# PowerSupply.net
KiCad netlist of a schematic drawn in EAGLE
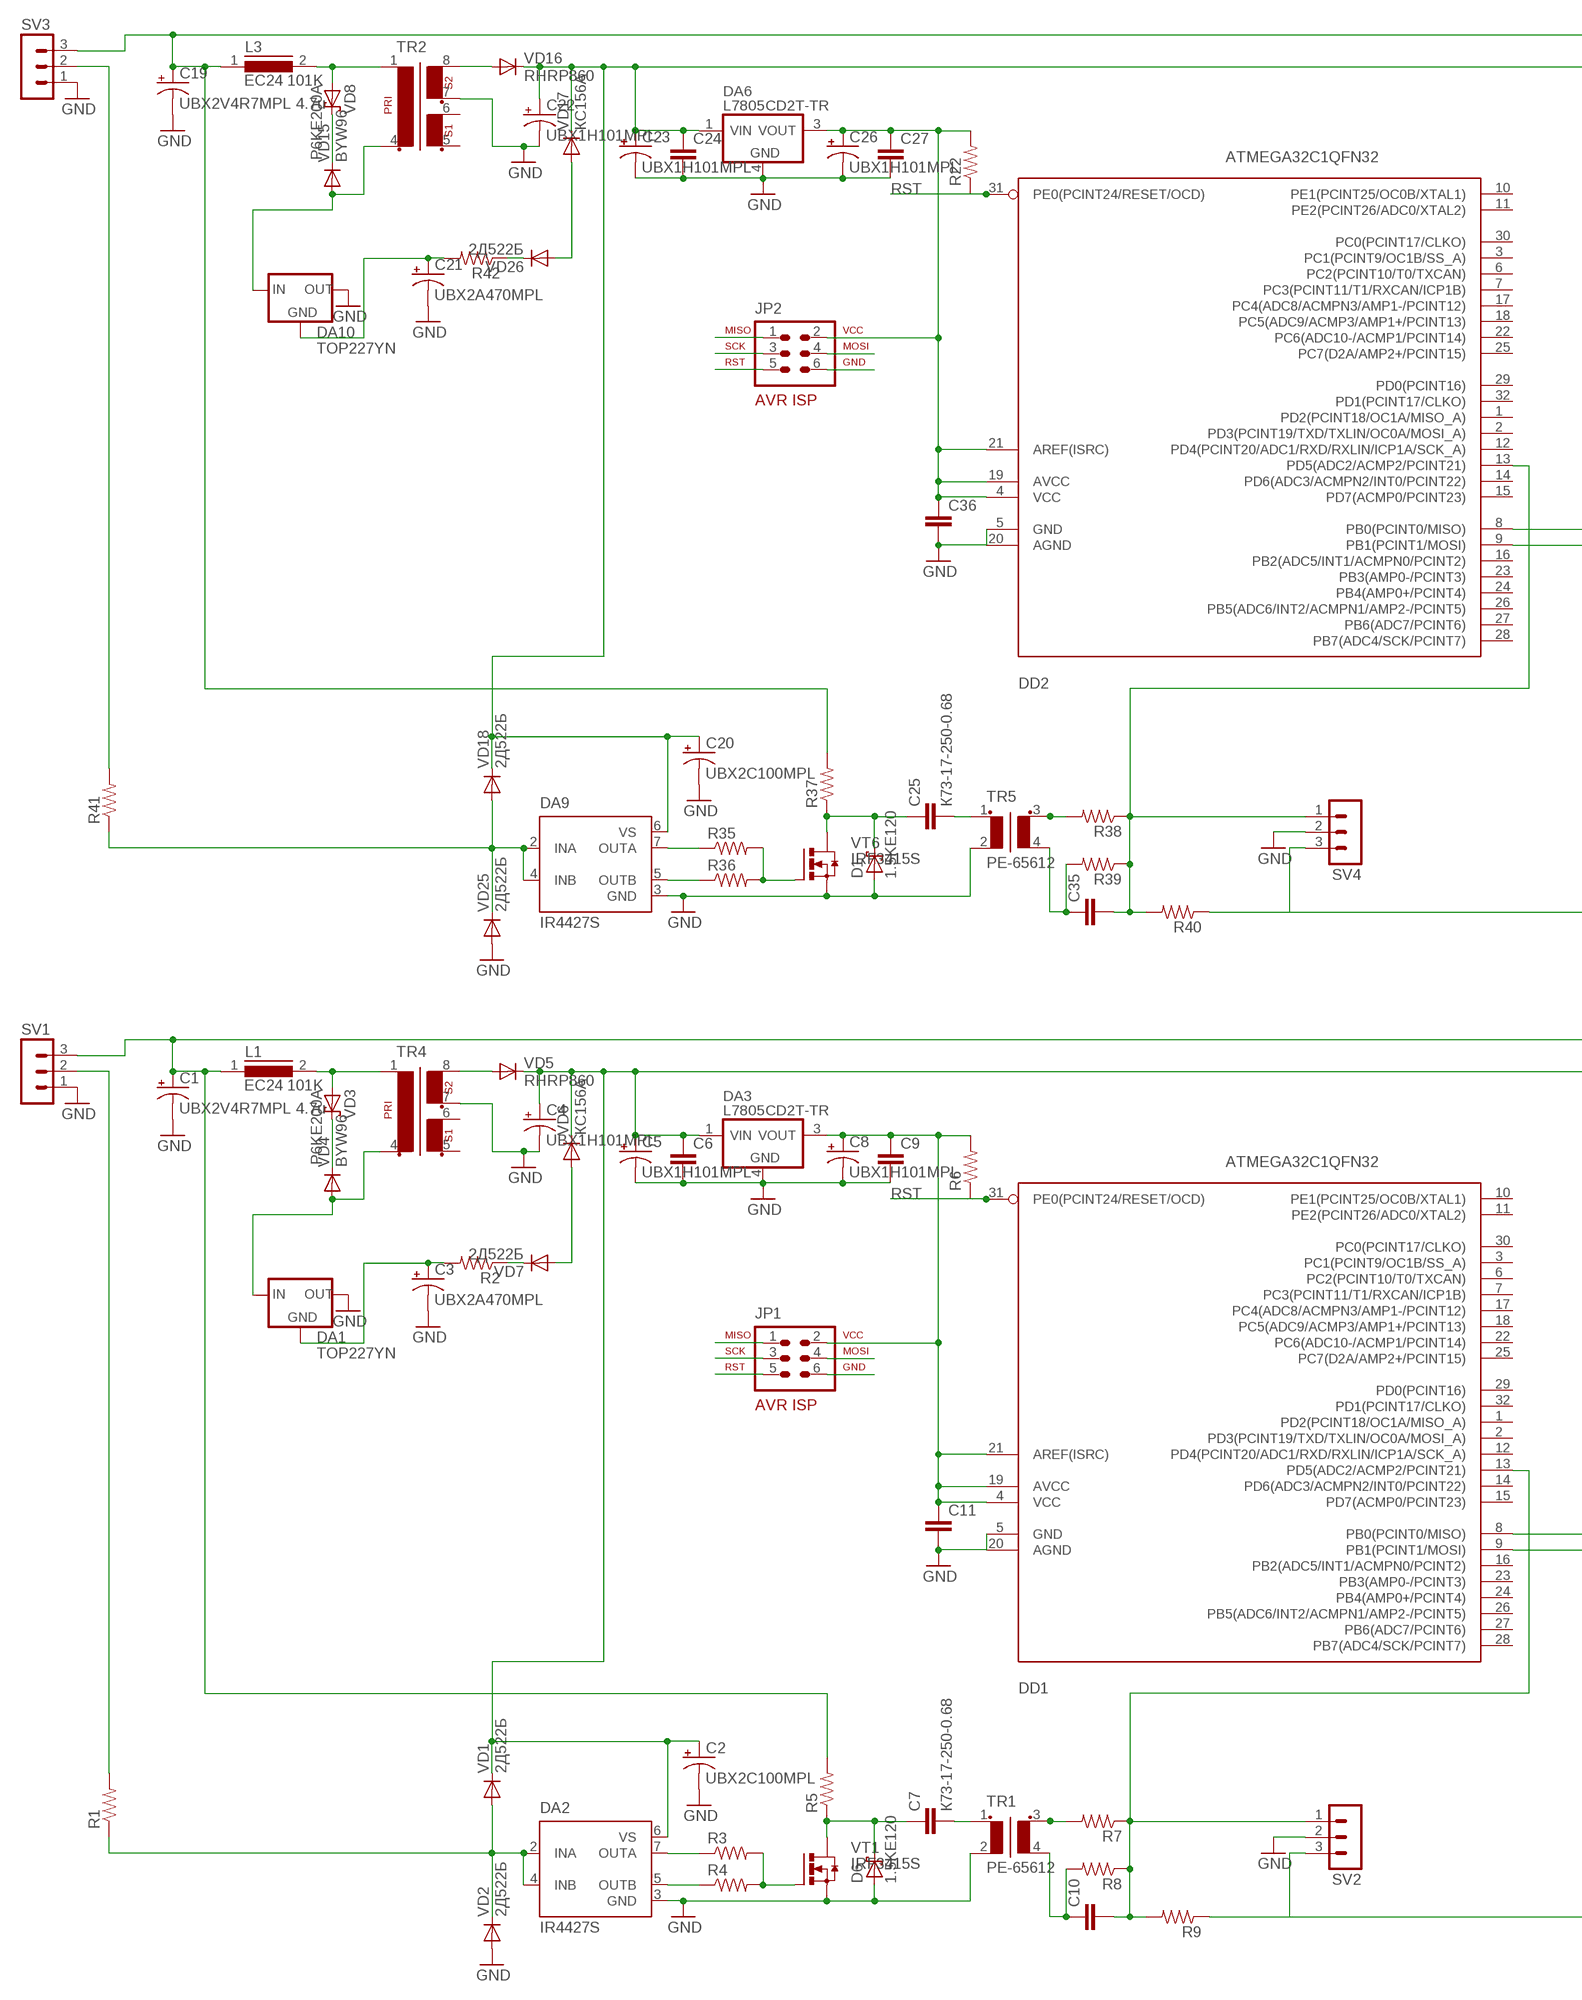
[diagram p0: schematic, sheet 1, part 1 of 2]
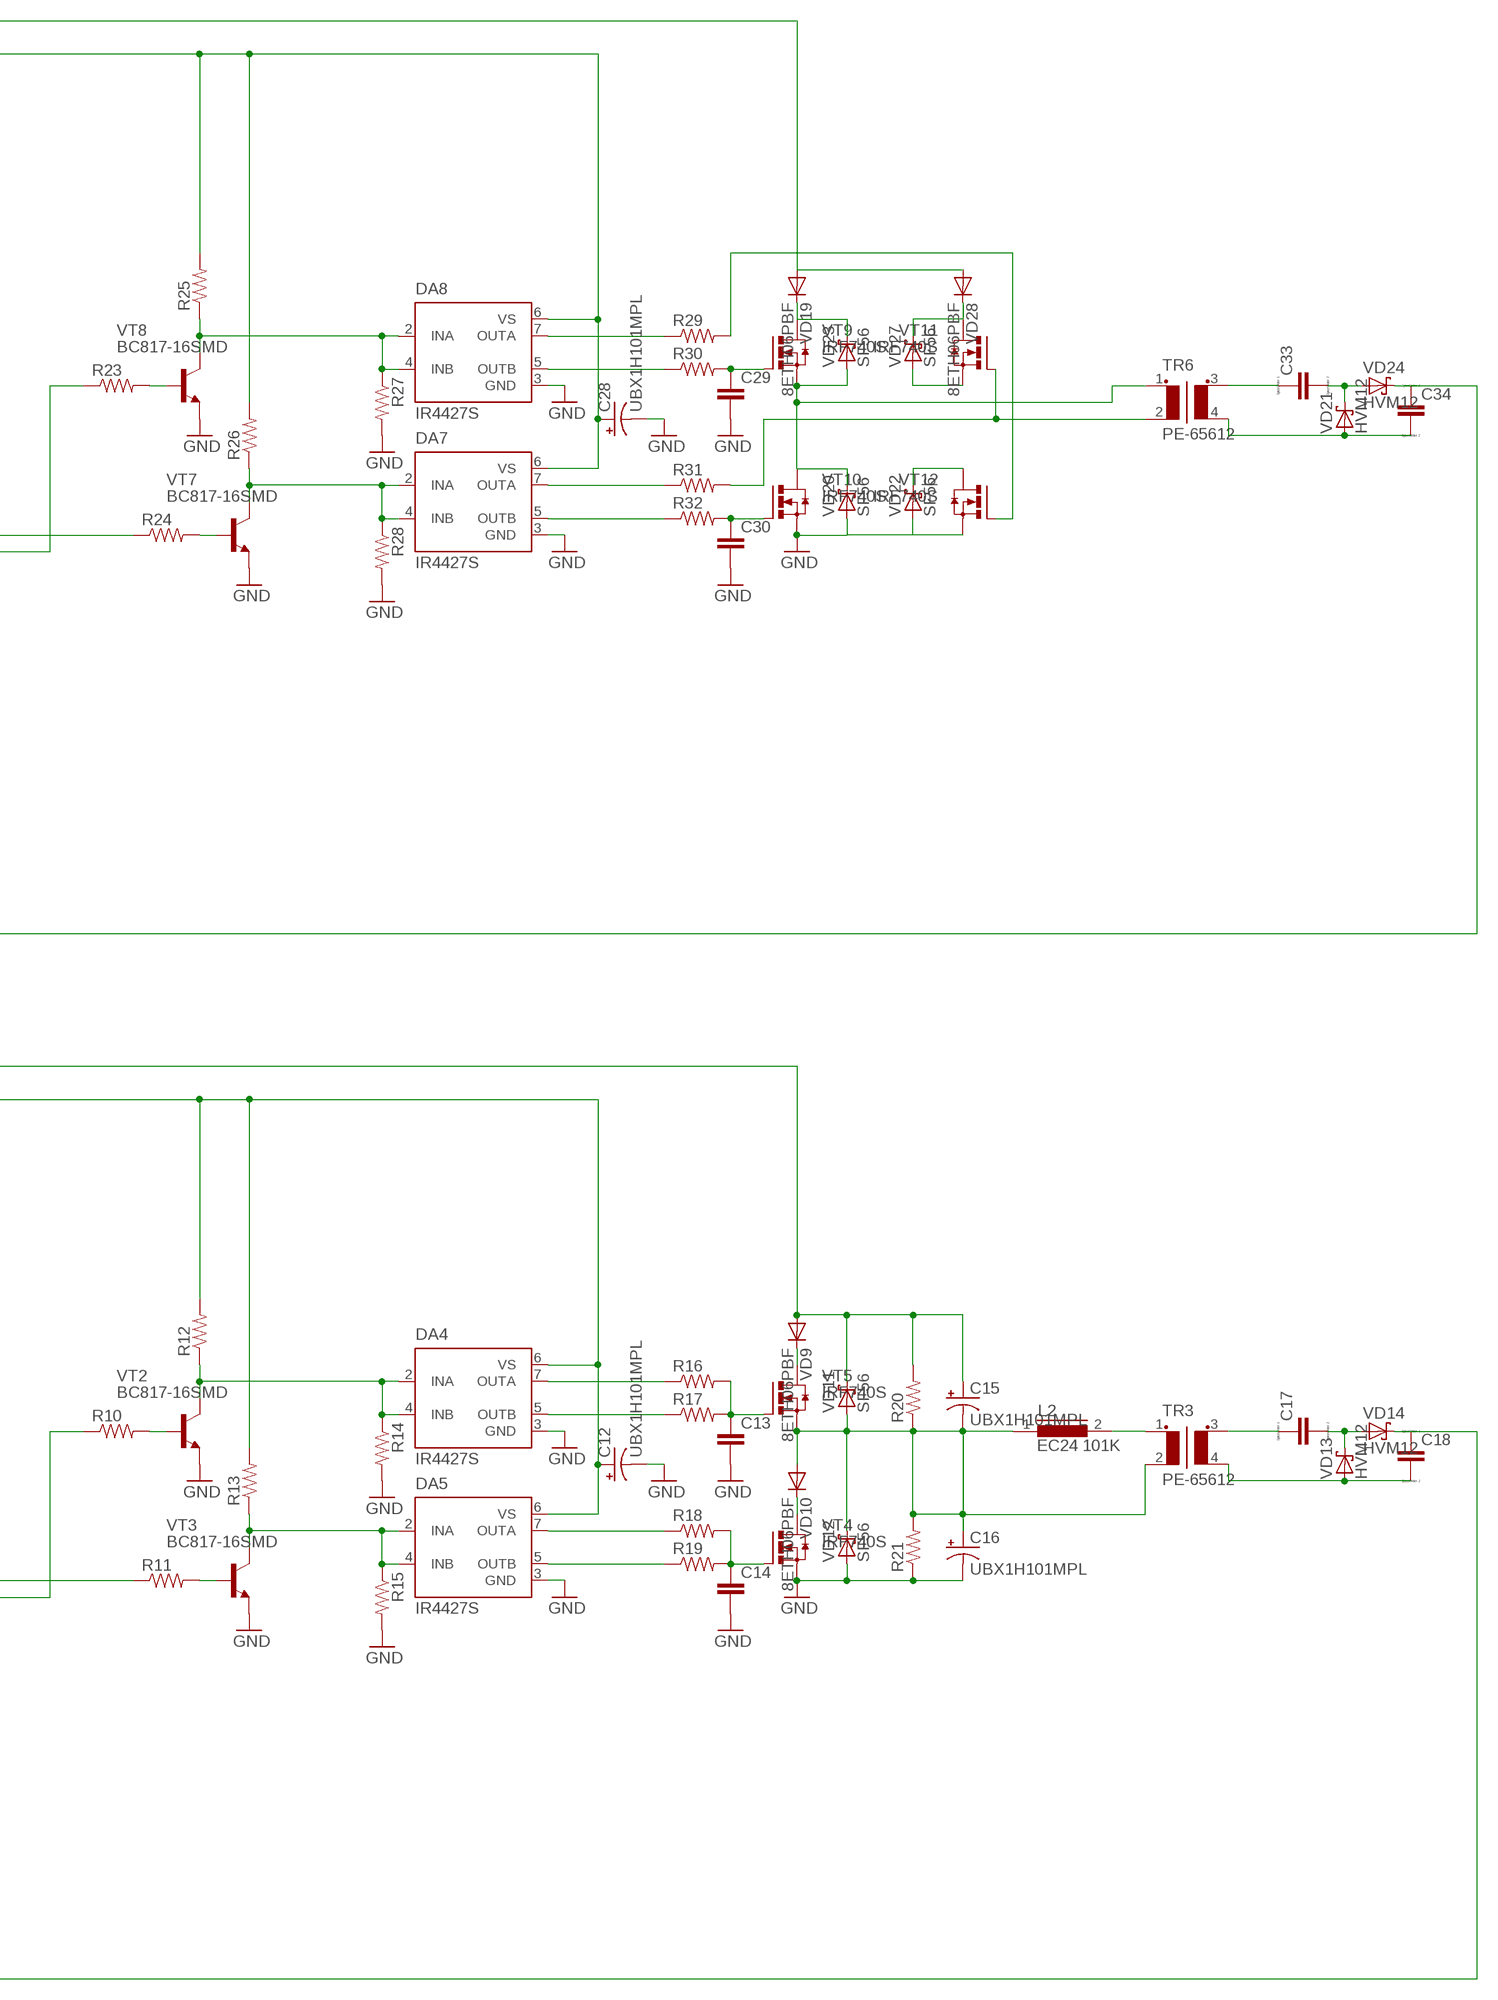
[diagram p1: schematic, sheet 1, part 2 of 2]

(export (version "E")
  (design (tool "Eeschema 10.0.6"))
  (components
    (comp (ref "C1")
      (value "UBX2V4R7MPL 4.7u")
      (footprint "eagle-import:CPOL-RADIAL-100UF-25V")
      (libsource (lib "eagle-import") (part "CAP_POLPTH1"))
    )
    (comp (ref "C2")
      (value "UBX2C100MPL")
      (footprint "eagle-import:CPOL-RADIAL-100UF-25V")
      (libsource (lib "eagle-import") (part "CAP_POLPTH1"))
    )
    (comp (ref "C3")
      (value "UBX2A470MPL")
      (footprint "eagle-import:CPOL-RADIAL-100UF-25V")
      (libsource (lib "eagle-import") (part "CAP_POLPTH1"))
    )
    (comp (ref "C4")
      (value "UBX1H101MPL")
      (footprint "eagle-import:CPOL-RADIAL-100UF-25V")
      (libsource (lib "eagle-import") (part "CAP_POLPTH1"))
    )
    (comp (ref "C5")
      (value "UBX1H101MPL")
      (footprint "eagle-import:CPOL-RADIAL-100UF-25V")
      (libsource (lib "eagle-import") (part "CAP_POLPTH1"))
    )
    (comp (ref "C6")
      (value "CAP1206")
      (footprint "eagle-import:1206")
      (libsource (lib "eagle-import") (part "CAP1206"))
    )
    (comp (ref "C7")
      (value "К73-17-250-0.68")
      (footprint "eagle-import:CAP-PTH-LARGE")
      (libsource (lib "eagle-import") (part "CAPPTH3"))
    )
    (comp (ref "C8")
      (value "UBX1H101MPL")
      (footprint "eagle-import:CPOL-RADIAL-100UF-25V")
      (libsource (lib "eagle-import") (part "CAP_POLPTH1"))
    )
    (comp (ref "C9")
      (value "CAP1206")
      (footprint "eagle-import:1206")
      (libsource (lib "eagle-import") (part "CAP1206"))
    )
    (comp (ref "C10")
      (value "CAP1206")
      (footprint "eagle-import:1206")
      (libsource (lib "eagle-import") (part "CAP1206"))
    )
    (comp (ref "C11")
      (value "CAP1206")
      (footprint "eagle-import:1206")
      (libsource (lib "eagle-import") (part "CAP1206"))
    )
    (comp (ref "C12")
      (value "UBX1H101MPL")
      (footprint "eagle-import:CPOL-RADIAL-100UF-25V")
      (libsource (lib "eagle-import") (part "CAP_POLPTH1"))
    )
    (comp (ref "C13")
      (value "CAP1206")
      (footprint "eagle-import:1206")
      (libsource (lib "eagle-import") (part "CAP1206"))
    )
    (comp (ref "C14")
      (value "CAP1206")
      (footprint "eagle-import:1206")
      (libsource (lib "eagle-import") (part "CAP1206"))
    )
    (comp (ref "C15")
      (value "UBX1H101MPL")
      (footprint "eagle-import:CPOL-RADIAL-100UF-25V")
      (libsource (lib "eagle-import") (part "CAP_POLPTH1"))
    )
    (comp (ref "C16")
      (value "UBX1H101MPL")
      (footprint "eagle-import:CPOL-RADIAL-100UF-25V")
      (libsource (lib "eagle-import") (part "CAP_POLPTH1"))
    )
    (comp (ref "C17")
      (value "CC1812")
      (footprint "eagle-import:C1812")
      (libsource (lib "eagle-import") (part "CC1812"))
    )
    (comp (ref "C18")
      (value "CC1812")
      (footprint "eagle-import:C1812")
      (libsource (lib "eagle-import") (part "CC1812"))
    )
    (comp (ref "C19")
      (value "UBX2V4R7MPL 4.7u")
      (footprint "eagle-import:CPOL-RADIAL-100UF-25V")
      (libsource (lib "eagle-import") (part "CAP_POLPTH1"))
    )
    (comp (ref "C20")
      (value "UBX2C100MPL")
      (footprint "eagle-import:CPOL-RADIAL-100UF-25V")
      (libsource (lib "eagle-import") (part "CAP_POLPTH1"))
    )
    (comp (ref "C21")
      (value "UBX2A470MPL")
      (footprint "eagle-import:CPOL-RADIAL-100UF-25V")
      (libsource (lib "eagle-import") (part "CAP_POLPTH1"))
    )
    (comp (ref "C22")
      (value "UBX1H101MPL")
      (footprint "eagle-import:CPOL-RADIAL-100UF-25V")
      (libsource (lib "eagle-import") (part "CAP_POLPTH1"))
    )
    (comp (ref "C23")
      (value "UBX1H101MPL")
      (footprint "eagle-import:CPOL-RADIAL-100UF-25V")
      (libsource (lib "eagle-import") (part "CAP_POLPTH1"))
    )
    (comp (ref "C24")
      (value "CAP1206")
      (footprint "eagle-import:1206")
      (libsource (lib "eagle-import") (part "CAP1206"))
    )
    (comp (ref "C25")
      (value "К73-17-250-0.68")
      (footprint "eagle-import:CAP-PTH-LARGE")
      (libsource (lib "eagle-import") (part "CAPPTH3"))
    )
    (comp (ref "C26")
      (value "UBX1H101MPL")
      (footprint "eagle-import:CPOL-RADIAL-100UF-25V")
      (libsource (lib "eagle-import") (part "CAP_POLPTH1"))
    )
    (comp (ref "C27")
      (value "CAP1206")
      (footprint "eagle-import:1206")
      (libsource (lib "eagle-import") (part "CAP1206"))
    )
    (comp (ref "C28")
      (value "UBX1H101MPL")
      (footprint "eagle-import:CPOL-RADIAL-100UF-25V")
      (libsource (lib "eagle-import") (part "CAP_POLPTH1"))
    )
    (comp (ref "C29")
      (value "CAP1206")
      (footprint "eagle-import:1206")
      (libsource (lib "eagle-import") (part "CAP1206"))
    )
    (comp (ref "C30")
      (value "CAP1206")
      (footprint "eagle-import:1206")
      (libsource (lib "eagle-import") (part "CAP1206"))
    )
    (comp (ref "C33")
      (value "CC1812")
      (footprint "eagle-import:C1812")
      (libsource (lib "eagle-import") (part "CC1812"))
    )
    (comp (ref "C34")
      (value "CC1812")
      (footprint "eagle-import:C1812")
      (libsource (lib "eagle-import") (part "CC1812"))
    )
    (comp (ref "C35")
      (value "CAP1206")
      (footprint "eagle-import:1206")
      (libsource (lib "eagle-import") (part "CAP1206"))
    )
    (comp (ref "C36")
      (value "CAP1206")
      (footprint "eagle-import:1206")
      (libsource (lib "eagle-import") (part "CAP1206"))
    )
    (comp (ref "D1")
      (value "1.5KE120")
      (footprint "eagle-import:CB417-15")
      (libsource (lib "eagle-import") (part "P6KEXX"))
    )
    (comp (ref "D6")
      (value "1.5KE120")
      (footprint "eagle-import:CB417-15")
      (libsource (lib "eagle-import") (part "P6KEXX"))
    )
    (comp (ref "DA1")
      (value "TOP227YN")
      (footprint "eagle-import:TO220S")
      (libsource (lib "eagle-import") (part "LM1086TO220V"))
    )
    (comp (ref "DA2")
      (value "IR4427S")
      (footprint "eagle-import:SO08")
      (fields (field (name "MF") "INTERNATIONAL RECTIFIER(IR)") (field (name "MPN") "IR4427STRPBF"))
      (libsource (lib "eagle-import") (part "IR4427S"))
    )
    (comp (ref "DA3")
      (value "L7805CD2T-TR")
      (footprint "eagle-import:D2PAK-3")
      (libsource (lib "eagle-import") (part "MC78D2T05"))
    )
    (comp (ref "DA4")
      (value "IR4427S")
      (footprint "eagle-import:SO08")
      (fields (field (name "MF") "INTERNATIONAL RECTIFIER(IR)") (field (name "MPN") "IR4427STRPBF"))
      (libsource (lib "eagle-import") (part "IR4427S"))
    )
    (comp (ref "DA5")
      (value "IR4427S")
      (footprint "eagle-import:SO08")
      (fields (field (name "MF") "INTERNATIONAL RECTIFIER(IR)") (field (name "MPN") "IR4427STRPBF"))
      (libsource (lib "eagle-import") (part "IR4427S"))
    )
    (comp (ref "DA6")
      (value "L7805CD2T-TR")
      (footprint "eagle-import:D2PAK-3")
      (libsource (lib "eagle-import") (part "MC78D2T05"))
    )
    (comp (ref "DA7")
      (value "IR4427S")
      (footprint "eagle-import:SO08")
      (fields (field (name "MF") "INTERNATIONAL RECTIFIER(IR)") (field (name "MPN") "IR4427STRPBF"))
      (libsource (lib "eagle-import") (part "IR4427S"))
    )
    (comp (ref "DA8")
      (value "IR4427S")
      (footprint "eagle-import:SO08")
      (fields (field (name "MF") "INTERNATIONAL RECTIFIER(IR)") (field (name "MPN") "IR4427STRPBF"))
      (libsource (lib "eagle-import") (part "IR4427S"))
    )
    (comp (ref "DA9")
      (value "IR4427S")
      (footprint "eagle-import:SO08")
      (fields (field (name "MF") "INTERNATIONAL RECTIFIER(IR)") (field (name "MPN") "IR4427STRPBF"))
      (libsource (lib "eagle-import") (part "IR4427S"))
    )
    (comp (ref "DA10")
      (value "TOP227YN")
      (footprint "eagle-import:TO220S")
      (libsource (lib "eagle-import") (part "LM1086TO220V"))
    )
    (comp (ref "DD1")
      (value "ATMEGA32C1QFN32")
      (footprint "eagle-import:QFN32")
      (libsource (lib "eagle-import") (part "ATMEGA32C1QFN32"))
    )
    (comp (ref "DD2")
      (value "ATMEGA32C1QFN32")
      (footprint "eagle-import:QFN32")
      (libsource (lib "eagle-import") (part "ATMEGA32C1QFN32"))
    )
    (comp (ref "JP1")
      (value "AVR-ISP-6VERT")
      (footprint "eagle-import:AVR-ISP-6")
      (libsource (lib "eagle-import") (part "AVR-ISP-6VERT"))
    )
    (comp (ref "JP2")
      (value "AVR-ISP-6VERT")
      (footprint "eagle-import:AVR-ISP-6")
      (libsource (lib "eagle-import") (part "AVR-ISP-6VERT"))
    )
    (comp (ref "L1")
      (value "EC24 101K")
      (footprint "eagle-import:MMICC7")
      (libsource (lib "eagle-import") (part "MMICC7"))
    )
    (comp (ref "L2")
      (value "EC24 101K")
      (footprint "eagle-import:MMICC7")
      (libsource (lib "eagle-import") (part "MMICC7"))
    )
    (comp (ref "L3")
      (value "EC24 101K")
      (footprint "eagle-import:MMICC7")
      (libsource (lib "eagle-import") (part "MMICC7"))
    )
    (comp (ref "R1")
      (value "RESISTOR1206")
      (footprint "eagle-import:1206")
      (libsource (lib "eagle-import") (part "RESISTOR1206"))
    )
    (comp (ref "R2")
      (value "RESISTOR1206")
      (footprint "eagle-import:1206")
      (libsource (lib "eagle-import") (part "RESISTOR1206"))
    )
    (comp (ref "R3")
      (value "RESISTOR1206")
      (footprint "eagle-import:1206")
      (libsource (lib "eagle-import") (part "RESISTOR1206"))
    )
    (comp (ref "R4")
      (value "RESISTOR1206")
      (footprint "eagle-import:1206")
      (libsource (lib "eagle-import") (part "RESISTOR1206"))
    )
    (comp (ref "R5")
      (value "RESISTOR1206")
      (footprint "eagle-import:1206")
      (libsource (lib "eagle-import") (part "RESISTOR1206"))
    )
    (comp (ref "R6")
      (value "RESISTOR1206")
      (footprint "eagle-import:1206")
      (libsource (lib "eagle-import") (part "RESISTOR1206"))
    )
    (comp (ref "R7")
      (value "RESISTOR1206")
      (footprint "eagle-import:1206")
      (libsource (lib "eagle-import") (part "RESISTOR1206"))
    )
    (comp (ref "R8")
      (value "RESISTOR1206")
      (footprint "eagle-import:1206")
      (libsource (lib "eagle-import") (part "RESISTOR1206"))
    )
    (comp (ref "R9")
      (value "RESISTOR1206")
      (footprint "eagle-import:1206")
      (libsource (lib "eagle-import") (part "RESISTOR1206"))
    )
    (comp (ref "R10")
      (value "RESISTOR1206")
      (footprint "eagle-import:1206")
      (libsource (lib "eagle-import") (part "RESISTOR1206"))
    )
    (comp (ref "R11")
      (value "RESISTOR1206")
      (footprint "eagle-import:1206")
      (libsource (lib "eagle-import") (part "RESISTOR1206"))
    )
    (comp (ref "R12")
      (value "RESISTOR1206")
      (footprint "eagle-import:1206")
      (libsource (lib "eagle-import") (part "RESISTOR1206"))
    )
    (comp (ref "R13")
      (value "RESISTOR1206")
      (footprint "eagle-import:1206")
      (libsource (lib "eagle-import") (part "RESISTOR1206"))
    )
    (comp (ref "R14")
      (value "RESISTOR1206")
      (footprint "eagle-import:1206")
      (libsource (lib "eagle-import") (part "RESISTOR1206"))
    )
    (comp (ref "R15")
      (value "RESISTOR1206")
      (footprint "eagle-import:1206")
      (libsource (lib "eagle-import") (part "RESISTOR1206"))
    )
    (comp (ref "R16")
      (value "RESISTOR1206")
      (footprint "eagle-import:1206")
      (libsource (lib "eagle-import") (part "RESISTOR1206"))
    )
    (comp (ref "R17")
      (value "RESISTOR1206")
      (footprint "eagle-import:1206")
      (libsource (lib "eagle-import") (part "RESISTOR1206"))
    )
    (comp (ref "R18")
      (value "RESISTOR1206")
      (footprint "eagle-import:1206")
      (libsource (lib "eagle-import") (part "RESISTOR1206"))
    )
    (comp (ref "R19")
      (value "RESISTOR1206")
      (footprint "eagle-import:1206")
      (libsource (lib "eagle-import") (part "RESISTOR1206"))
    )
    (comp (ref "R20")
      (value "RESISTOR1206")
      (footprint "eagle-import:1206")
      (libsource (lib "eagle-import") (part "RESISTOR1206"))
    )
    (comp (ref "R21")
      (value "RESISTOR1206")
      (footprint "eagle-import:1206")
      (libsource (lib "eagle-import") (part "RESISTOR1206"))
    )
    (comp (ref "R22")
      (value "RESISTOR1206")
      (footprint "eagle-import:1206")
      (libsource (lib "eagle-import") (part "RESISTOR1206"))
    )
    (comp (ref "R23")
      (value "RESISTOR1206")
      (footprint "eagle-import:1206")
      (libsource (lib "eagle-import") (part "RESISTOR1206"))
    )
    (comp (ref "R24")
      (value "RESISTOR1206")
      (footprint "eagle-import:1206")
      (libsource (lib "eagle-import") (part "RESISTOR1206"))
    )
    (comp (ref "R25")
      (value "RESISTOR1206")
      (footprint "eagle-import:1206")
      (libsource (lib "eagle-import") (part "RESISTOR1206"))
    )
    (comp (ref "R26")
      (value "RESISTOR1206")
      (footprint "eagle-import:1206")
      (libsource (lib "eagle-import") (part "RESISTOR1206"))
    )
    (comp (ref "R27")
      (value "RESISTOR1206")
      (footprint "eagle-import:1206")
      (libsource (lib "eagle-import") (part "RESISTOR1206"))
    )
    (comp (ref "R28")
      (value "RESISTOR1206")
      (footprint "eagle-import:1206")
      (libsource (lib "eagle-import") (part "RESISTOR1206"))
    )
    (comp (ref "R29")
      (value "RESISTOR1206")
      (footprint "eagle-import:1206")
      (libsource (lib "eagle-import") (part "RESISTOR1206"))
    )
    (comp (ref "R30")
      (value "RESISTOR1206")
      (footprint "eagle-import:1206")
      (libsource (lib "eagle-import") (part "RESISTOR1206"))
    )
    (comp (ref "R31")
      (value "RESISTOR1206")
      (footprint "eagle-import:1206")
      (libsource (lib "eagle-import") (part "RESISTOR1206"))
    )
    (comp (ref "R32")
      (value "RESISTOR1206")
      (footprint "eagle-import:1206")
      (libsource (lib "eagle-import") (part "RESISTOR1206"))
    )
    (comp (ref "R35")
      (value "RESISTOR1206")
      (footprint "eagle-import:1206")
      (libsource (lib "eagle-import") (part "RESISTOR1206"))
    )
    (comp (ref "R36")
      (value "RESISTOR1206")
      (footprint "eagle-import:1206")
      (libsource (lib "eagle-import") (part "RESISTOR1206"))
    )
    (comp (ref "R37")
      (value "RESISTOR1206")
      (footprint "eagle-import:1206")
      (libsource (lib "eagle-import") (part "RESISTOR1206"))
    )
    (comp (ref "R38")
      (value "RESISTOR1206")
      (footprint "eagle-import:1206")
      (libsource (lib "eagle-import") (part "RESISTOR1206"))
    )
    (comp (ref "R39")
      (value "RESISTOR1206")
      (footprint "eagle-import:1206")
      (libsource (lib "eagle-import") (part "RESISTOR1206"))
    )
    (comp (ref "R40")
      (value "RESISTOR1206")
      (footprint "eagle-import:1206")
      (libsource (lib "eagle-import") (part "RESISTOR1206"))
    )
    (comp (ref "R41")
      (value "RESISTOR1206")
      (footprint "eagle-import:1206")
      (libsource (lib "eagle-import") (part "RESISTOR1206"))
    )
    (comp (ref "R42")
      (value "RESISTOR1206")
      (footprint "eagle-import:1206")
      (libsource (lib "eagle-import") (part "RESISTOR1206"))
    )
    (comp (ref "SV1")
      (value "MA03-1")
      (footprint "eagle-import:MA03-1")
      (libsource (lib "eagle-import") (part "MA03-1"))
    )
    (comp (ref "SV2")
      (value "MA03-1")
      (footprint "eagle-import:MA03-1")
      (libsource (lib "eagle-import") (part "MA03-1"))
    )
    (comp (ref "SV3")
      (value "MA03-1")
      (footprint "eagle-import:MA03-1")
      (libsource (lib "eagle-import") (part "MA03-1"))
    )
    (comp (ref "SV4")
      (value "MA03-1")
      (footprint "eagle-import:MA03-1")
      (libsource (lib "eagle-import") (part "MA03-1"))
    )
    (comp (ref "TR1")
      (value "PE-65612")
      (footprint "eagle-import:PE-65612")
      (libsource (lib "eagle-import") (part "PE-65612"))
    )
    (comp (ref "TR2")
      (value "EE20-2")
      (footprint "eagle-import:EE20-2")
      (libsource (lib "eagle-import") (part "EE20-2"))
    )
    (comp (ref "TR3")
      (value "PE-65612")
      (footprint "eagle-import:PE-65612")
      (libsource (lib "eagle-import") (part "PE-65612"))
    )
    (comp (ref "TR4")
      (value "EE20-2")
      (footprint "eagle-import:EE20-2")
      (libsource (lib "eagle-import") (part "EE20-2"))
    )
    (comp (ref "TR5")
      (value "PE-65612")
      (footprint "eagle-import:PE-65612")
      (libsource (lib "eagle-import") (part "PE-65612"))
    )
    (comp (ref "TR6")
      (value "PE-65612")
      (footprint "eagle-import:PE-65612")
      (libsource (lib "eagle-import") (part "PE-65612"))
    )
    (comp (ref "VD1")
      (value "2Д522Б")
      (footprint "eagle-import:DO35-10")
      (libsource (lib "eagle-import") (part "1N4446"))
    )
    (comp (ref "VD2")
      (value "2Д522Б")
      (footprint "eagle-import:DO35-10")
      (libsource (lib "eagle-import") (part "1N4446"))
    )
    (comp (ref "VD3")
      (value "P6KE200A")
      (footprint "eagle-import:CB417-15")
      (libsource (lib "eagle-import") (part "P6KEXX"))
    )
    (comp (ref "VD4")
      (value "BYW96")
      (footprint "eagle-import:SOD64-10")
      (libsource (lib "eagle-import") (part "BYW96"))
    )
    (comp (ref "VD5")
      (value "RHRP860")
      (footprint "eagle-import:TO220ACS")
      (libsource (lib "eagle-import") (part "DIODE-TO220V"))
    )
    (comp (ref "VD6")
      (value "КС156А")
      (footprint "eagle-import:DO35-10")
      (libsource (lib "eagle-import") (part "1N4446"))
    )
    (comp (ref "VD7")
      (value "2Д522Б")
      (footprint "eagle-import:DO35-10")
      (libsource (lib "eagle-import") (part "1N4446"))
    )
    (comp (ref "VD8")
      (value "P6KE200A")
      (footprint "eagle-import:CB417-15")
      (libsource (lib "eagle-import") (part "P6KEXX"))
    )
    (comp (ref "VD9")
      (value "8ETH06PBF")
      (footprint "eagle-import:TO220ACS")
      (libsource (lib "eagle-import") (part "DIODE-TO220V"))
    )
    (comp (ref "VD10")
      (value "8ETH06PBF")
      (footprint "eagle-import:TO220ACS")
      (libsource (lib "eagle-import") (part "DIODE-TO220V"))
    )
    (comp (ref "VD11")
      (value "SF56")
      (footprint "eagle-import:CB417-15")
      (libsource (lib "eagle-import") (part "P6KEXX"))
    )
    (comp (ref "VD12")
      (value "SF56")
      (footprint "eagle-import:CB417-15")
      (libsource (lib "eagle-import") (part "P6KEXX"))
    )
    (comp (ref "VD13")
      (value "HVM12")
      (footprint "eagle-import:CB417-15")
      (libsource (lib "eagle-import") (part "P6KEXX"))
    )
    (comp (ref "VD14")
      (value "HVM12")
      (footprint "eagle-import:CB417-15")
      (libsource (lib "eagle-import") (part "P6KEXX"))
    )
    (comp (ref "VD15")
      (value "BYW96")
      (footprint "eagle-import:SOD64-10")
      (libsource (lib "eagle-import") (part "BYW96"))
    )
    (comp (ref "VD16")
      (value "RHRP860")
      (footprint "eagle-import:TO220ACS")
      (libsource (lib "eagle-import") (part "DIODE-TO220V"))
    )
    (comp (ref "VD17")
      (value "КС156А")
      (footprint "eagle-import:DO35-10")
      (libsource (lib "eagle-import") (part "1N4446"))
    )
    (comp (ref "VD18")
      (value "2Д522Б")
      (footprint "eagle-import:DO35-10")
      (libsource (lib "eagle-import") (part "1N4446"))
    )
    (comp (ref "VD19")
      (value "8ETH06PBF")
      (footprint "eagle-import:TO220ACS")
      (libsource (lib "eagle-import") (part "DIODE-TO220V"))
    )
    (comp (ref "VD20")
      (value "SF56")
      (footprint "eagle-import:CB417-15")
      (libsource (lib "eagle-import") (part "P6KEXX"))
    )
    (comp (ref "VD21")
      (value "HVM12")
      (footprint "eagle-import:CB417-15")
      (libsource (lib "eagle-import") (part "P6KEXX"))
    )
    (comp (ref "VD22")
      (value "SF56")
      (footprint "eagle-import:CB417-15")
      (libsource (lib "eagle-import") (part "P6KEXX"))
    )
    (comp (ref "VD23")
      (value "SF56")
      (footprint "eagle-import:CB417-15")
      (libsource (lib "eagle-import") (part "P6KEXX"))
    )
    (comp (ref "VD24")
      (value "HVM12")
      (footprint "eagle-import:CB417-15")
      (libsource (lib "eagle-import") (part "P6KEXX"))
    )
    (comp (ref "VD25")
      (value "2Д522Б")
      (footprint "eagle-import:DO35-10")
      (libsource (lib "eagle-import") (part "1N4446"))
    )
    (comp (ref "VD26")
      (value "2Д522Б")
      (footprint "eagle-import:DO35-10")
      (libsource (lib "eagle-import") (part "1N4446"))
    )
    (comp (ref "VD27")
      (value "SF56")
      (footprint "eagle-import:CB417-15")
      (libsource (lib "eagle-import") (part "P6KEXX"))
    )
    (comp (ref "VD28")
      (value "8ETH06PBF")
      (footprint "eagle-import:TO220ACS")
      (libsource (lib "eagle-import") (part "DIODE-TO220V"))
    )
    (comp (ref "VT1")
      (value "IRF3415S")
      (footprint "eagle-import:D2PACK")
      (libsource (lib "eagle-import") (part "IRF3704S"))
    )
    (comp (ref "VT2")
      (value "BC817-16SMD")
      (footprint "eagle-import:SOT23-BEC")
      (libsource (lib "eagle-import") (part "BC817SMD-16"))
    )
    (comp (ref "VT3")
      (value "BC817-16SMD")
      (footprint "eagle-import:SOT23-BEC")
      (libsource (lib "eagle-import") (part "BC817SMD-16"))
    )
    (comp (ref "VT4")
      (value "IRF740S")
      (footprint "eagle-import:D2PACK")
      (libsource (lib "eagle-import") (part "IRF3704S"))
    )
    (comp (ref "VT5")
      (value "IRF740S")
      (footprint "eagle-import:D2PACK")
      (libsource (lib "eagle-import") (part "IRF3704S"))
    )
    (comp (ref "VT6")
      (value "IRF3415S")
      (footprint "eagle-import:D2PACK")
      (libsource (lib "eagle-import") (part "IRF3704S"))
    )
    (comp (ref "VT7")
      (value "BC817-16SMD")
      (footprint "eagle-import:SOT23-BEC")
      (libsource (lib "eagle-import") (part "BC817SMD-16"))
    )
    (comp (ref "VT8")
      (value "BC817-16SMD")
      (footprint "eagle-import:SOT23-BEC")
      (libsource (lib "eagle-import") (part "BC817SMD-16"))
    )
    (comp (ref "VT9")
      (value "IRF740S")
      (footprint "eagle-import:D2PACK")
      (libsource (lib "eagle-import") (part "IRF3704S"))
    )
    (comp (ref "VT10")
      (value "IRF740S")
      (footprint "eagle-import:D2PACK")
      (libsource (lib "eagle-import") (part "IRF3704S"))
    )
    (comp (ref "VT11")
      (value "IRF740S")
      (footprint "eagle-import:D2PACK")
      (libsource (lib "eagle-import") (part "IRF3704S"))
    )
    (comp (ref "VT12")
      (value "IRF740S")
      (footprint "eagle-import:D2PACK")
      (libsource (lib "eagle-import") (part "IRF3704S"))
    )
  )
  (nets
    (net (code "1") (name "/MISO") (class "Default")
      (node (ref "DD1") (pin "8") (pinfunction "PB0(PCINT0/MISO)_8") (pintype "bidirectional"))
      (node (ref "JP1") (pin "1") (pinfunction "1_1") (pintype "passive"))
      (node (ref "R11") (pin "1") (pinfunction "1_1") (pintype "passive"))
    )
    (net (code "2") (name "/MISO1") (class "Default")
      (node (ref "DD2") (pin "8") (pinfunction "PB0(PCINT0/MISO)_8") (pintype "bidirectional"))
      (node (ref "JP2") (pin "1") (pinfunction "1_1") (pintype "passive"))
      (node (ref "R24") (pin "1") (pinfunction "1_1") (pintype "passive"))
    )
    (net (code "3") (name "/MOSI") (class "Default")
      (node (ref "DD1") (pin "9") (pinfunction "PB1(PCINT1/MOSI)_9") (pintype "bidirectional"))
      (node (ref "JP1") (pin "4") (pinfunction "4_4") (pintype "passive"))
      (node (ref "R10") (pin "1") (pinfunction "1_1") (pintype "passive"))
    )
    (net (code "4") (name "/MOSI1") (class "Default")
      (node (ref "DD2") (pin "9") (pinfunction "PB1(PCINT1/MOSI)_9") (pintype "bidirectional"))
      (node (ref "JP2") (pin "4") (pinfunction "4_4") (pintype "passive"))
      (node (ref "R23") (pin "1") (pinfunction "1_1") (pintype "passive"))
    )
    (net (code "5") (name "/RST") (class "Default")
      (node (ref "DD1") (pin "31") (pinfunction "PE0(PCINT24/RESET/OCD)_31") (pintype "bidirectional"))
      (node (ref "DD2") (pin "31") (pinfunction "PE0(PCINT24/RESET/OCD)_31") (pintype "bidirectional"))
      (node (ref "JP1") (pin "5") (pinfunction "5_5") (pintype "passive"))
      (node (ref "JP2") (pin "5") (pinfunction "5_5") (pintype "passive"))
      (node (ref "R22") (pin "1") (pinfunction "1_1") (pintype "passive"))
      (node (ref "R6") (pin "1") (pinfunction "1_1") (pintype "passive"))
    )
    (net (code "6") (name "/VOUT") (class "Default")
      (node (ref "C11") (pin "1") (pinfunction "1_1") (pintype "passive"))
      (node (ref "C26") (pin "1") (pinfunction "+_1") (pintype "passive"))
      (node (ref "C27") (pin "1") (pinfunction "1_1") (pintype "passive"))
      (node (ref "C36") (pin "1") (pinfunction "1_1") (pintype "passive"))
      (node (ref "C8") (pin "1") (pinfunction "+_1") (pintype "passive"))
      (node (ref "C9") (pin "1") (pinfunction "1_1") (pintype "passive"))
      (node (ref "DA3") (pin "3") (pinfunction "VOUT_3") (pintype "power_in"))
      (node (ref "DA6") (pin "3") (pinfunction "VOUT_3") (pintype "power_in"))
      (node (ref "DD1") (pin "19") (pinfunction "AVCC_19") (pintype "bidirectional"))
      (node (ref "DD1") (pin "21") (pinfunction "AREF(ISRC)_21") (pintype "bidirectional"))
      (node (ref "DD1") (pin "4") (pinfunction "VCC_4") (pintype "bidirectional"))
      (node (ref "DD2") (pin "19") (pinfunction "AVCC_19") (pintype "bidirectional"))
      (node (ref "DD2") (pin "21") (pinfunction "AREF(ISRC)_21") (pintype "bidirectional"))
      (node (ref "DD2") (pin "4") (pinfunction "VCC_4") (pintype "bidirectional"))
      (node (ref "JP1") (pin "2") (pinfunction "2_2") (pintype "passive"))
      (node (ref "JP2") (pin "2") (pinfunction "2_2") (pintype "passive"))
      (node (ref "R22") (pin "2") (pinfunction "2_2") (pintype "passive"))
      (node (ref "R6") (pin "2") (pinfunction "2_2") (pintype "passive"))
    )
    (net (code "7") (name "GND") (class "Default")
      (node (ref "C1") (pin "2") (pinfunction "-_2") (pintype "passive"))
      (node (ref "C11") (pin "2") (pinfunction "2_2") (pintype "passive"))
      (node (ref "C12") (pin "2") (pinfunction "-_2") (pintype "passive"))
      (node (ref "C13") (pin "2") (pinfunction "2_2") (pintype "passive"))
      (node (ref "C14") (pin "2") (pinfunction "2_2") (pintype "passive"))
      (node (ref "C16") (pin "2") (pinfunction "-_2") (pintype "passive"))
      (node (ref "C19") (pin "2") (pinfunction "-_2") (pintype "passive"))
      (node (ref "C2") (pin "2") (pinfunction "-_2") (pintype "passive"))
      (node (ref "C20") (pin "2") (pinfunction "-_2") (pintype "passive"))
      (node (ref "C21") (pin "2") (pinfunction "-_2") (pintype "passive"))
      (node (ref "C22") (pin "2") (pinfunction "-_2") (pintype "passive"))
      (node (ref "C23") (pin "2") (pinfunction "-_2") (pintype "passive"))
      (node (ref "C24") (pin "2") (pinfunction "2_2") (pintype "passive"))
      (node (ref "C26") (pin "2") (pinfunction "-_2") (pintype "passive"))
      (node (ref "C27") (pin "2") (pinfunction "2_2") (pintype "passive"))
      (node (ref "C28") (pin "2") (pinfunction "-_2") (pintype "passive"))
      (node (ref "C29") (pin "2") (pinfunction "2_2") (pintype "passive"))
      (node (ref "C3") (pin "2") (pinfunction "-_2") (pintype "passive"))
      (node (ref "C30") (pin "2") (pinfunction "2_2") (pintype "passive"))
      (node (ref "C36") (pin "2") (pinfunction "2_2") (pintype "passive"))
      (node (ref "C4") (pin "2") (pinfunction "-_2") (pintype "passive"))
      (node (ref "C5") (pin "2") (pinfunction "-_2") (pintype "passive"))
      (node (ref "C6") (pin "2") (pinfunction "2_2") (pintype "passive"))
      (node (ref "C8") (pin "2") (pinfunction "-_2") (pintype "passive"))
      (node (ref "C9") (pin "2") (pinfunction "2_2") (pintype "passive"))
      (node (ref "D1") (pin "A") (pinfunction "A_A") (pintype "passive"))
      (node (ref "D6") (pin "A") (pinfunction "A_A") (pintype "passive"))
      (node (ref "DA1") (pin "2") (pinfunction "OUT_2") (pintype "passive"))
      (node (ref "DA10") (pin "2") (pinfunction "OUT_2") (pintype "passive"))
      (node (ref "DA2") (pin "3") (pinfunction "GND_3") (pintype "power_in"))
      (node (ref "DA3") (pin "4") (pinfunction "GND_4") (pintype "power_in"))
      (node (ref "DA4") (pin "3") (pinfunction "GND_3") (pintype "power_in"))
      (node (ref "DA5") (pin "3") (pinfunction "GND_3") (pintype "power_in"))
      (node (ref "DA6") (pin "4") (pinfunction "GND_4") (pintype "power_in"))
      (node (ref "DA7") (pin "3") (pinfunction "GND_3") (pintype "power_in"))
      (node (ref "DA8") (pin "3") (pinfunction "GND_3") (pintype "power_in"))
      (node (ref "DA9") (pin "3") (pinfunction "GND_3") (pintype "power_in"))
      (node (ref "DD1") (pin "20") (pinfunction "AGND_20") (pintype "bidirectional"))
      (node (ref "DD1") (pin "5") (pinfunction "GND_5") (pintype "bidirectional"))
      (node (ref "DD2") (pin "20") (pinfunction "AGND_20") (pintype "bidirectional"))
      (node (ref "DD2") (pin "5") (pinfunction "GND_5") (pintype "bidirectional"))
      (node (ref "JP1") (pin "6") (pinfunction "6_6") (pintype "passive"))
      (node (ref "JP2") (pin "6") (pinfunction "6_6") (pintype "passive"))
      (node (ref "R14") (pin "2") (pinfunction "2_2") (pintype "passive"))
      (node (ref "R15") (pin "2") (pinfunction "2_2") (pintype "passive"))
      (node (ref "R21") (pin "1") (pinfunction "1_1") (pintype "passive"))
      (node (ref "R27") (pin "2") (pinfunction "2_2") (pintype "passive"))
      (node (ref "R28") (pin "2") (pinfunction "2_2") (pintype "passive"))
      (node (ref "SV1") (pin "1") (pinfunction "1_1") (pintype "passive"))
      (node (ref "SV2") (pin "2") (pinfunction "2_2") (pintype "passive"))
      (node (ref "SV3") (pin "1") (pinfunction "1_1") (pintype "passive"))
      (node (ref "SV4") (pin "2") (pinfunction "2_2") (pintype "passive"))
      (node (ref "TR1") (pin "2") (pinfunction "P2_2") (pintype "passive"))
      (node (ref "TR2") (pin "7") (pinfunction "5_7") (pintype "passive"))
      (node (ref "TR4") (pin "7") (pinfunction "5_7") (pintype "passive"))
      (node (ref "TR5") (pin "2") (pinfunction "P2_2") (pintype "passive"))
      (node (ref "VD12") (pin "A") (pinfunction "A_A") (pintype "passive"))
      (node (ref "VD2") (pin "A") (pinfunction "A_A") (pintype "passive"))
      (node (ref "VD20") (pin "A") (pinfunction "A_A") (pintype "passive"))
      (node (ref "VD22") (pin "A") (pinfunction "A_A") (pintype "passive"))
      (node (ref "VD25") (pin "A") (pinfunction "A_A") (pintype "passive"))
      (node (ref "VT1") (pin "3") (pinfunction "S_3") (pintype "passive"))
      (node (ref "VT10") (pin "3") (pinfunction "S_3") (pintype "passive"))
      (node (ref "VT12") (pin "3") (pinfunction "S_3") (pintype "passive"))
      (node (ref "VT2") (pin "E") (pinfunction "E_E") (pintype "passive"))
      (node (ref "VT3") (pin "E") (pinfunction "E_E") (pintype "passive"))
      (node (ref "VT4") (pin "3") (pinfunction "S_3") (pintype "passive"))
      (node (ref "VT6") (pin "3") (pinfunction "S_3") (pintype "passive"))
      (node (ref "VT7") (pin "E") (pinfunction "E_E") (pintype "passive"))
      (node (ref "VT8") (pin "E") (pinfunction "E_E") (pintype "passive"))
    )
    (net (code "8") (name "Net-(C1-+)") (class "Default")
      (node (ref "C1") (pin "1") (pinfunction "+_1") (pintype "passive"))
      (node (ref "C15") (pin "1") (pinfunction "+_1") (pintype "passive"))
      (node (ref "L1") (pin "1") (pinfunction "1_1") (pintype "passive"))
      (node (ref "R20") (pin "2") (pinfunction "2_2") (pintype "passive"))
      (node (ref "R5") (pin "2") (pinfunction "2_2") (pintype "passive"))
      (node (ref "SV1") (pin "3") (pinfunction "3_3") (pintype "passive"))
      (node (ref "VD11") (pin "C") (pinfunction "C_C") (pintype "passive"))
      (node (ref "VD9") (pin "A") (pinfunction "A_A") (pintype "passive"))
    )
    (net (code "9") (name "Net-(C3-+)") (class "Default")
      (node (ref "C3") (pin "1") (pinfunction "+_1") (pintype "passive"))
      (node (ref "DA1") (pin "1") (pinfunction "GND_1") (pintype "input"))
      (node (ref "R2") (pin "2") (pinfunction "2_2") (pintype "passive"))
    )
    (net (code "10") (name "Net-(C12-+)") (class "Default")
      (node (ref "C12") (pin "1") (pinfunction "+_1") (pintype "passive"))
      (node (ref "C2") (pin "1") (pinfunction "+_1") (pintype "passive"))
      (node (ref "C4") (pin "1") (pinfunction "+_1") (pintype "passive"))
      (node (ref "C5") (pin "1") (pinfunction "+_1") (pintype "passive"))
      (node (ref "C6") (pin "1") (pinfunction "1_1") (pintype "passive"))
      (node (ref "DA2") (pin "6") (pinfunction "VS_6") (pintype "power_in"))
      (node (ref "DA3") (pin "1") (pinfunction "VIN_1") (pintype "power_in"))
      (node (ref "DA4") (pin "6") (pinfunction "VS_6") (pintype "power_in"))
      (node (ref "DA5") (pin "6") (pinfunction "VS_6") (pintype "power_in"))
      (node (ref "R12") (pin "2") (pinfunction "2_2") (pintype "passive"))
      (node (ref "R13") (pin "2") (pinfunction "2_2") (pintype "passive"))
      (node (ref "VD1") (pin "C") (pinfunction "C_C") (pintype "passive"))
      (node (ref "VD5") (pin "C") (pinfunction "C_C") (pintype "passive"))
      (node (ref "VD6") (pin "C") (pinfunction "C_C") (pintype "passive"))
    )
    (net (code "11") (name "Net-(C15--)") (class "Default")
      (node (ref "C15") (pin "2") (pinfunction "-_2") (pintype "passive"))
      (node (ref "C16") (pin "1") (pinfunction "+_1") (pintype "passive"))
      (node (ref "L2") (pin "1") (pinfunction "1_1") (pintype "passive"))
      (node (ref "R20") (pin "1") (pinfunction "1_1") (pintype "passive"))
      (node (ref "R21") (pin "2") (pinfunction "2_2") (pintype "passive"))
      (node (ref "TR3") (pin "2") (pinfunction "P2_2") (pintype "passive"))
      (node (ref "VD10") (pin "A") (pinfunction "A_A") (pintype "passive"))
      (node (ref "VD11") (pin "A") (pinfunction "A_A") (pintype "passive"))
      (node (ref "VD12") (pin "C") (pinfunction "C_C") (pintype "passive"))
      (node (ref "VT5") (pin "3") (pinfunction "S_3") (pintype "passive"))
    )
    (net (code "12") (name "Net-(C17-Pad2)") (class "Default")
      (node (ref "C17") (pin "2") (pinfunction "2_2") (pintype "passive"))
      (node (ref "VD13") (pin "C") (pinfunction "C_C") (pintype "passive"))
      (node (ref "VD14") (pin "A") (pinfunction "A_A") (pintype "passive"))
    )
    (net (code "13") (name "Net-(C18-Pad1)") (class "Default")
      (node (ref "C18") (pin "1") (pinfunction "1_1") (pintype "passive"))
      (node (ref "R9") (pin "1") (pinfunction "1_1") (pintype "passive"))
      (node (ref "SV2") (pin "3") (pinfunction "3_3") (pintype "passive"))
      (node (ref "VD14") (pin "C") (pinfunction "C_C") (pintype "passive"))
    )
    (net (code "14") (name "Net-(C19-+)") (class "Default")
      (node (ref "C19") (pin "1") (pinfunction "+_1") (pintype "passive"))
      (node (ref "L3") (pin "1") (pinfunction "1_1") (pintype "passive"))
      (node (ref "R37") (pin "2") (pinfunction "2_2") (pintype "passive"))
      (node (ref "SV3") (pin "3") (pinfunction "3_3") (pintype "passive"))
      (node (ref "VD19") (pin "A") (pinfunction "A_A") (pintype "passive"))
      (node (ref "VD28") (pin "A") (pinfunction "A_A") (pintype "passive"))
    )
    (net (code "15") (name "Net-(C20-+)") (class "Default")
      (node (ref "C20") (pin "1") (pinfunction "+_1") (pintype "passive"))
      (node (ref "C22") (pin "1") (pinfunction "+_1") (pintype "passive"))
      (node (ref "C23") (pin "1") (pinfunction "+_1") (pintype "passive"))
      (node (ref "C24") (pin "1") (pinfunction "1_1") (pintype "passive"))
      (node (ref "C28") (pin "1") (pinfunction "+_1") (pintype "passive"))
      (node (ref "DA6") (pin "1") (pinfunction "VIN_1") (pintype "power_in"))
      (node (ref "DA7") (pin "6") (pinfunction "VS_6") (pintype "power_in"))
      (node (ref "DA8") (pin "6") (pinfunction "VS_6") (pintype "power_in"))
      (node (ref "DA9") (pin "6") (pinfunction "VS_6") (pintype "power_in"))
      (node (ref "R25") (pin "2") (pinfunction "2_2") (pintype "passive"))
      (node (ref "R26") (pin "2") (pinfunction "2_2") (pintype "passive"))
      (node (ref "VD16") (pin "C") (pinfunction "C_C") (pintype "passive"))
      (node (ref "VD17") (pin "C") (pinfunction "C_C") (pintype "passive"))
      (node (ref "VD18") (pin "C") (pinfunction "C_C") (pintype "passive"))
    )
    (net (code "16") (name "Net-(C21-+)") (class "Default")
      (node (ref "C21") (pin "1") (pinfunction "+_1") (pintype "passive"))
      (node (ref "DA10") (pin "1") (pinfunction "GND_1") (pintype "input"))
      (node (ref "R42") (pin "2") (pinfunction "2_2") (pintype "passive"))
    )
    (net (code "17") (name "Net-(C33-Pad2)") (class "Default")
      (node (ref "C33") (pin "2") (pinfunction "2_2") (pintype "passive"))
      (node (ref "VD21") (pin "C") (pinfunction "C_C") (pintype "passive"))
      (node (ref "VD24") (pin "A") (pinfunction "A_A") (pintype "passive"))
    )
    (net (code "18") (name "Net-(C34-Pad1)") (class "Default")
      (node (ref "C34") (pin "1") (pinfunction "1_1") (pintype "passive"))
      (node (ref "R40") (pin "1") (pinfunction "1_1") (pintype "passive"))
      (node (ref "SV4") (pin "3") (pinfunction "3_3") (pintype "passive"))
      (node (ref "VD24") (pin "C") (pinfunction "C_C") (pintype "passive"))
    )
    (net (code "19") (name "Net-(DA1-IN)") (class "Default")
      (node (ref "DA1") (pin "3") (pinfunction "IN_3") (pintype "input"))
      (node (ref "TR4") (pin "4") (pinfunction "2_4") (pintype "passive"))
      (node (ref "VD4") (pin "A") (pinfunction "A_A") (pintype "passive"))
    )
    (net (code "20") (name "Net-(DA2-INA)") (class "Default")
      (node (ref "DA2") (pin "2") (pinfunction "INA_2") (pintype "input"))
      (node (ref "DA2") (pin "4") (pinfunction "INB_4") (pintype "input"))
      (node (ref "R1") (pin "1") (pinfunction "1_1") (pintype "passive"))
      (node (ref "VD1") (pin "A") (pinfunction "A_A") (pintype "passive"))
      (node (ref "VD2") (pin "C") (pinfunction "C_C") (pintype "passive"))
    )
    (net (code "21") (name "Net-(DA2-OUTA)") (class "Default")
      (node (ref "DA2") (pin "7") (pinfunction "OUTA_7") (pintype "output"))
      (node (ref "R3") (pin "1") (pinfunction "1_1") (pintype "passive"))
    )
    (net (code "22") (name "Net-(DA2-OUTB)") (class "Default")
      (node (ref "DA2") (pin "5") (pinfunction "OUTB_5") (pintype "output"))
      (node (ref "R4") (pin "1") (pinfunction "1_1") (pintype "passive"))
    )
    (net (code "23") (name "Net-(DA4-INA)") (class "Default")
      (node (ref "DA4") (pin "2") (pinfunction "INA_2") (pintype "input"))
      (node (ref "DA4") (pin "4") (pinfunction "INB_4") (pintype "input"))
      (node (ref "R12") (pin "1") (pinfunction "1_1") (pintype "passive"))
      (node (ref "R14") (pin "1") (pinfunction "1_1") (pintype "passive"))
      (node (ref "VT2") (pin "C") (pinfunction "C_C") (pintype "passive"))
    )
    (net (code "24") (name "Net-(DA4-OUTA)") (class "Default")
      (node (ref "DA4") (pin "7") (pinfunction "OUTA_7") (pintype "output"))
      (node (ref "R16") (pin "1") (pinfunction "1_1") (pintype "passive"))
    )
    (net (code "25") (name "Net-(DA4-OUTB)") (class "Default")
      (node (ref "DA4") (pin "5") (pinfunction "OUTB_5") (pintype "output"))
      (node (ref "R17") (pin "1") (pinfunction "1_1") (pintype "passive"))
    )
    (net (code "26") (name "Net-(DA5-INA)") (class "Default")
      (node (ref "DA5") (pin "2") (pinfunction "INA_2") (pintype "input"))
      (node (ref "DA5") (pin "4") (pinfunction "INB_4") (pintype "input"))
      (node (ref "R13") (pin "1") (pinfunction "1_1") (pintype "passive"))
      (node (ref "R15") (pin "1") (pinfunction "1_1") (pintype "passive"))
      (node (ref "VT3") (pin "C") (pinfunction "C_C") (pintype "passive"))
    )
    (net (code "27") (name "Net-(DA5-OUTA)") (class "Default")
      (node (ref "DA5") (pin "7") (pinfunction "OUTA_7") (pintype "output"))
      (node (ref "R18") (pin "1") (pinfunction "1_1") (pintype "passive"))
    )
    (net (code "28") (name "Net-(DA5-OUTB)") (class "Default")
      (node (ref "DA5") (pin "5") (pinfunction "OUTB_5") (pintype "output"))
      (node (ref "R19") (pin "1") (pinfunction "1_1") (pintype "passive"))
    )
    (net (code "29") (name "Net-(DA7-INA)") (class "Default")
      (node (ref "DA7") (pin "2") (pinfunction "INA_2") (pintype "input"))
      (node (ref "DA7") (pin "4") (pinfunction "INB_4") (pintype "input"))
      (node (ref "R26") (pin "1") (pinfunction "1_1") (pintype "passive"))
      (node (ref "R28") (pin "1") (pinfunction "1_1") (pintype "passive"))
      (node (ref "VT7") (pin "C") (pinfunction "C_C") (pintype "passive"))
    )
    (net (code "30") (name "Net-(DA7-OUTA)") (class "Default")
      (node (ref "DA7") (pin "7") (pinfunction "OUTA_7") (pintype "output"))
      (node (ref "R31") (pin "1") (pinfunction "1_1") (pintype "passive"))
    )
    (net (code "31") (name "Net-(DA7-OUTB)") (class "Default")
      (node (ref "DA7") (pin "5") (pinfunction "OUTB_5") (pintype "output"))
      (node (ref "R32") (pin "1") (pinfunction "1_1") (pintype "passive"))
    )
    (net (code "32") (name "Net-(DA8-INA)") (class "Default")
      (node (ref "DA8") (pin "2") (pinfunction "INA_2") (pintype "input"))
      (node (ref "DA8") (pin "4") (pinfunction "INB_4") (pintype "input"))
      (node (ref "R25") (pin "1") (pinfunction "1_1") (pintype "passive"))
      (node (ref "R27") (pin "1") (pinfunction "1_1") (pintype "passive"))
      (node (ref "VT8") (pin "C") (pinfunction "C_C") (pintype "passive"))
    )
    (net (code "33") (name "Net-(DA8-OUTA)") (class "Default")
      (node (ref "DA8") (pin "7") (pinfunction "OUTA_7") (pintype "output"))
      (node (ref "R29") (pin "1") (pinfunction "1_1") (pintype "passive"))
    )
    (net (code "34") (name "Net-(DA8-OUTB)") (class "Default")
      (node (ref "DA8") (pin "5") (pinfunction "OUTB_5") (pintype "output"))
      (node (ref "R30") (pin "1") (pinfunction "1_1") (pintype "passive"))
    )
    (net (code "35") (name "Net-(DA9-INA)") (class "Default")
      (node (ref "DA9") (pin "2") (pinfunction "INA_2") (pintype "input"))
      (node (ref "DA9") (pin "4") (pinfunction "INB_4") (pintype "input"))
      (node (ref "R41") (pin "1") (pinfunction "1_1") (pintype "passive"))
      (node (ref "VD18") (pin "A") (pinfunction "A_A") (pintype "passive"))
      (node (ref "VD25") (pin "C") (pinfunction "C_C") (pintype "passive"))
    )
    (net (code "36") (name "Net-(DA9-OUTA)") (class "Default")
      (node (ref "DA9") (pin "7") (pinfunction "OUTA_7") (pintype "output"))
      (node (ref "R35") (pin "1") (pinfunction "1_1") (pintype "passive"))
    )
    (net (code "37") (name "Net-(DA9-OUTB)") (class "Default")
      (node (ref "DA9") (pin "5") (pinfunction "OUTB_5") (pintype "output"))
      (node (ref "R36") (pin "1") (pinfunction "1_1") (pintype "passive"))
    )
    (net (code "38") (name "Net-(DA10-IN)") (class "Default")
      (node (ref "DA10") (pin "3") (pinfunction "IN_3") (pintype "input"))
      (node (ref "TR2") (pin "4") (pinfunction "2_4") (pintype "passive"))
      (node (ref "VD15") (pin "A") (pinfunction "A_A") (pintype "passive"))
    )
    (net (code "39") (name "Net-(DD1-PD5(ADC2{slash}ACMP2{slash}PCINT21))") (class "Default")
      (node (ref "C10") (pin "2") (pinfunction "2_2") (pintype "passive"))
      (node (ref "DD1") (pin "13") (pinfunction "PD5(ADC2/ACMP2/PCINT21)_13") (pintype "bidirectional"))
      (node (ref "R7") (pin "1") (pinfunction "1_1") (pintype "passive"))
      (node (ref "R8") (pin "1") (pinfunction "1_1") (pintype "passive"))
      (node (ref "R9") (pin "2") (pinfunction "2_2") (pintype "passive"))
      (node (ref "SV2") (pin "1") (pinfunction "1_1") (pintype "passive"))
    )
    (net (code "40") (name "Net-(DD2-PD5(ADC2{slash}ACMP2{slash}PCINT21))") (class "Default")
      (node (ref "C35") (pin "2") (pinfunction "2_2") (pintype "passive"))
      (node (ref "DD2") (pin "13") (pinfunction "PD5(ADC2/ACMP2/PCINT21)_13") (pintype "bidirectional"))
      (node (ref "R38") (pin "1") (pinfunction "1_1") (pintype "passive"))
      (node (ref "R39") (pin "1") (pinfunction "1_1") (pintype "passive"))
      (node (ref "R40") (pin "2") (pinfunction "2_2") (pintype "passive"))
      (node (ref "SV4") (pin "1") (pinfunction "1_1") (pintype "passive"))
    )
    (net (code "41") (name "Net-(L1-Pad2)") (class "Default")
      (node (ref "L1") (pin "2") (pinfunction "2_2") (pintype "passive"))
      (node (ref "TR4") (pin "1") (pinfunction "1_1") (pintype "passive"))
      (node (ref "VD3") (pin "A") (pinfunction "A_A") (pintype "passive"))
    )
    (net (code "42") (name "Net-(L3-Pad2)") (class "Default")
      (node (ref "L3") (pin "2") (pinfunction "2_2") (pintype "passive"))
      (node (ref "TR2") (pin "1") (pinfunction "1_1") (pintype "passive"))
      (node (ref "VD8") (pin "A") (pinfunction "A_A") (pintype "passive"))
    )
    (net (code "43") (name "Net-(R1-Pad2)") (class "Default")
      (node (ref "R1") (pin "2") (pinfunction "2_2") (pintype "passive"))
      (node (ref "SV1") (pin "2") (pinfunction "2_2") (pintype "passive"))
    )
    (net (code "44") (name "Net-(R2-Pad1)") (class "Default")
      (node (ref "R2") (pin "1") (pinfunction "1_1") (pintype "passive"))
      (node (ref "VD7") (pin "C") (pinfunction "C_C") (pintype "passive"))
    )
    (net (code "45") (name "Net-(R10-Pad2)") (class "Default")
      (node (ref "R10") (pin "2") (pinfunction "2_2") (pintype "passive"))
      (node (ref "VT2") (pin "B") (pinfunction "B_B") (pintype "passive"))
    )
    (net (code "46") (name "Net-(R11-Pad2)") (class "Default")
      (node (ref "R11") (pin "2") (pinfunction "2_2") (pintype "passive"))
      (node (ref "VT3") (pin "B") (pinfunction "B_B") (pintype "passive"))
    )
    (net (code "47") (name "Net-(R23-Pad2)") (class "Default")
      (node (ref "R23") (pin "2") (pinfunction "2_2") (pintype "passive"))
      (node (ref "VT8") (pin "B") (pinfunction "B_B") (pintype "passive"))
    )
    (net (code "48") (name "Net-(R24-Pad2)") (class "Default")
      (node (ref "R24") (pin "2") (pinfunction "2_2") (pintype "passive"))
      (node (ref "VT7") (pin "B") (pinfunction "B_B") (pintype "passive"))
    )
    (net (code "49") (name "Net-(R41-Pad2)") (class "Default")
      (node (ref "R41") (pin "2") (pinfunction "2_2") (pintype "passive"))
      (node (ref "SV3") (pin "2") (pinfunction "2_2") (pintype "passive"))
    )
    (net (code "50") (name "Net-(R42-Pad1)") (class "Default")
      (node (ref "R42") (pin "1") (pinfunction "1_1") (pintype "passive"))
      (node (ref "VD26") (pin "C") (pinfunction "C_C") (pintype "passive"))
    )
    (net (code "51") (name "Net-(TR1-P1)") (class "Default")
      (node (ref "C7") (pin "2") (pinfunction "2_2") (pintype "passive"))
      (node (ref "TR1") (pin "1") (pinfunction "P1_1") (pintype "passive"))
    )
    (net (code "52") (name "Net-(TR1-S1)") (class "Default")
      (node (ref "R7") (pin "2") (pinfunction "2_2") (pintype "passive"))
      (node (ref "TR1") (pin "3") (pinfunction "S1_3") (pintype "passive"))
    )
    (net (code "53") (name "Net-(TR1-S2)") (class "Default")
      (node (ref "C10") (pin "1") (pinfunction "1_1") (pintype "passive"))
      (node (ref "R8") (pin "2") (pinfunction "2_2") (pintype "passive"))
      (node (ref "TR1") (pin "4") (pinfunction "S2_4") (pintype "passive"))
    )
    (net (code "54") (name "Net-(TR2-6)") (class "Default")
      (node (ref "TR2") (pin "8") (pinfunction "6_8") (pintype "passive"))
      (node (ref "VD16") (pin "A") (pinfunction "A_A") (pintype "passive"))
    )
    (net (code "55") (name "Net-(TR3-P1)") (class "Default")
      (node (ref "L2") (pin "2") (pinfunction "2_2") (pintype "passive"))
      (node (ref "TR3") (pin "1") (pinfunction "P1_1") (pintype "passive"))
    )
    (net (code "56") (name "Net-(TR3-S1)") (class "Default")
      (node (ref "C17") (pin "1") (pinfunction "1_1") (pintype "passive"))
      (node (ref "TR3") (pin "3") (pinfunction "S1_3") (pintype "passive"))
    )
    (net (code "57") (name "Net-(TR3-S2)") (class "Default")
      (node (ref "C18") (pin "2") (pinfunction "2_2") (pintype "passive"))
      (node (ref "TR3") (pin "4") (pinfunction "S2_4") (pintype "passive"))
      (node (ref "VD13") (pin "A") (pinfunction "A_A") (pintype "passive"))
    )
    (net (code "58") (name "Net-(TR4-6)") (class "Default")
      (node (ref "TR4") (pin "8") (pinfunction "6_8") (pintype "passive"))
      (node (ref "VD5") (pin "A") (pinfunction "A_A") (pintype "passive"))
    )
    (net (code "59") (name "Net-(TR5-P1)") (class "Default")
      (node (ref "C25") (pin "2") (pinfunction "2_2") (pintype "passive"))
      (node (ref "TR5") (pin "1") (pinfunction "P1_1") (pintype "passive"))
    )
    (net (code "60") (name "Net-(TR5-S1)") (class "Default")
      (node (ref "R38") (pin "2") (pinfunction "2_2") (pintype "passive"))
      (node (ref "TR5") (pin "3") (pinfunction "S1_3") (pintype "passive"))
    )
    (net (code "61") (name "Net-(TR5-S2)") (class "Default")
      (node (ref "C35") (pin "1") (pinfunction "1_1") (pintype "passive"))
      (node (ref "R39") (pin "2") (pinfunction "2_2") (pintype "passive"))
      (node (ref "TR5") (pin "4") (pinfunction "S2_4") (pintype "passive"))
    )
    (net (code "62") (name "Net-(TR6-P1)") (class "Default")
      (node (ref "TR6") (pin "1") (pinfunction "P1_1") (pintype "passive"))
      (node (ref "VD20") (pin "C") (pinfunction "C_C") (pintype "passive"))
      (node (ref "VD23") (pin "A") (pinfunction "A_A") (pintype "passive"))
      (node (ref "VT10") (pin "2") (pinfunction "D_2") (pintype "passive"))
      (node (ref "VT9") (pin "3") (pinfunction "S_3") (pintype "passive"))
    )
    (net (code "63") (name "Net-(TR6-P2)") (class "Default")
      (node (ref "R31") (pin "2") (pinfunction "2_2") (pintype "passive"))
      (node (ref "TR6") (pin "2") (pinfunction "P2_2") (pintype "passive"))
      (node (ref "VT11") (pin "1") (pinfunction "G_1") (pintype "passive"))
    )
    (net (code "64") (name "Net-(TR6-S1)") (class "Default")
      (node (ref "C33") (pin "1") (pinfunction "1_1") (pintype "passive"))
      (node (ref "TR6") (pin "3") (pinfunction "S1_3") (pintype "passive"))
    )
    (net (code "65") (name "Net-(TR6-S2)") (class "Default")
      (node (ref "C34") (pin "2") (pinfunction "2_2") (pintype "passive"))
      (node (ref "TR6") (pin "4") (pinfunction "S2_4") (pintype "passive"))
      (node (ref "VD21") (pin "A") (pinfunction "A_A") (pintype "passive"))
    )
    (net (code "66") (name "Net-(VD3-PadC)") (class "Default")
      (node (ref "VD3") (pin "C") (pinfunction "C_C") (pintype "passive"))
      (node (ref "VD4") (pin "C") (pinfunction "C_C") (pintype "passive"))
    )
    (net (code "67") (name "Net-(VD6-PadA)") (class "Default")
      (node (ref "VD6") (pin "A") (pinfunction "A_A") (pintype "passive"))
      (node (ref "VD7") (pin "A") (pinfunction "A_A") (pintype "passive"))
    )
    (net (code "68") (name "Net-(VD15-PadC)") (class "Default")
      (node (ref "VD15") (pin "C") (pinfunction "C_C") (pintype "passive"))
      (node (ref "VD8") (pin "C") (pinfunction "C_C") (pintype "passive"))
    )
    (net (code "69") (name "Net-(VD17-PadA)") (class "Default")
      (node (ref "VD17") (pin "A") (pinfunction "A_A") (pintype "passive"))
      (node (ref "VD26") (pin "A") (pinfunction "A_A") (pintype "passive"))
    )
    (net (code "70") (name "Net-(VT1-D)") (class "Default")
      (node (ref "C7") (pin "1") (pinfunction "1_1") (pintype "passive"))
      (node (ref "D6") (pin "C") (pinfunction "C_C") (pintype "passive"))
      (node (ref "R5") (pin "1") (pinfunction "1_1") (pintype "passive"))
      (node (ref "VT1") (pin "2") (pinfunction "D_2") (pintype "passive"))
    )
    (net (code "71") (name "Net-(VT1-G)") (class "Default")
      (node (ref "R3") (pin "2") (pinfunction "2_2") (pintype "passive"))
      (node (ref "R4") (pin "2") (pinfunction "2_2") (pintype "passive"))
      (node (ref "VT1") (pin "1") (pinfunction "G_1") (pintype "passive"))
    )
    (net (code "72") (name "Net-(VT4-D)") (class "Default")
      (node (ref "VD10") (pin "C") (pinfunction "C_C") (pintype "passive"))
      (node (ref "VT4") (pin "2") (pinfunction "D_2") (pintype "passive"))
    )
    (net (code "73") (name "Net-(VT4-G)") (class "Default")
      (node (ref "C14") (pin "1") (pinfunction "1_1") (pintype "passive"))
      (node (ref "R18") (pin "2") (pinfunction "2_2") (pintype "passive"))
      (node (ref "R19") (pin "2") (pinfunction "2_2") (pintype "passive"))
      (node (ref "VT4") (pin "1") (pinfunction "G_1") (pintype "passive"))
    )
    (net (code "74") (name "Net-(VT5-D)") (class "Default")
      (node (ref "VD9") (pin "C") (pinfunction "C_C") (pintype "passive"))
      (node (ref "VT5") (pin "2") (pinfunction "D_2") (pintype "passive"))
    )
    (net (code "75") (name "Net-(VT5-G)") (class "Default")
      (node (ref "C13") (pin "1") (pinfunction "1_1") (pintype "passive"))
      (node (ref "R16") (pin "2") (pinfunction "2_2") (pintype "passive"))
      (node (ref "R17") (pin "2") (pinfunction "2_2") (pintype "passive"))
      (node (ref "VT5") (pin "1") (pinfunction "G_1") (pintype "passive"))
    )
    (net (code "76") (name "Net-(VT6-D)") (class "Default")
      (node (ref "C25") (pin "1") (pinfunction "1_1") (pintype "passive"))
      (node (ref "D1") (pin "C") (pinfunction "C_C") (pintype "passive"))
      (node (ref "R37") (pin "1") (pinfunction "1_1") (pintype "passive"))
      (node (ref "VT6") (pin "2") (pinfunction "D_2") (pintype "passive"))
    )
    (net (code "77") (name "Net-(VT6-G)") (class "Default")
      (node (ref "R35") (pin "2") (pinfunction "2_2") (pintype "passive"))
      (node (ref "R36") (pin "2") (pinfunction "2_2") (pintype "passive"))
      (node (ref "VT6") (pin "1") (pinfunction "G_1") (pintype "passive"))
    )
    (net (code "78") (name "Net-(VT9-D)") (class "Default")
      (node (ref "VD19") (pin "C") (pinfunction "C_C") (pintype "passive"))
      (node (ref "VD23") (pin "C") (pinfunction "C_C") (pintype "passive"))
      (node (ref "VT9") (pin "2") (pinfunction "D_2") (pintype "passive"))
    )
    (net (code "79") (name "Net-(VT9-G)") (class "Default")
      (node (ref "C29") (pin "1") (pinfunction "1_1") (pintype "passive"))
      (node (ref "R30") (pin "2") (pinfunction "2_2") (pintype "passive"))
      (node (ref "VT9") (pin "1") (pinfunction "G_1") (pintype "passive"))
    )
    (net (code "80") (name "Net-(VT10-G)") (class "Default")
      (node (ref "C30") (pin "1") (pinfunction "1_1") (pintype "passive"))
      (node (ref "R32") (pin "2") (pinfunction "2_2") (pintype "passive"))
      (node (ref "VT10") (pin "1") (pinfunction "G_1") (pintype "passive"))
    )
    (net (code "81") (name "Net-(VT11-D)") (class "Default")
      (node (ref "VD27") (pin "C") (pinfunction "C_C") (pintype "passive"))
      (node (ref "VD28") (pin "C") (pinfunction "C_C") (pintype "passive"))
      (node (ref "VT11") (pin "2") (pinfunction "D_2") (pintype "passive"))
    )
    (net (code "82") (name "Net-(VT11-S)") (class "Default")
      (node (ref "VD27") (pin "A") (pinfunction "A_A") (pintype "passive"))
      (node (ref "VT11") (pin "3") (pinfunction "S_3") (pintype "passive"))
    )
    (net (code "83") (name "Net-(VT12-D)") (class "Default")
      (node (ref "VD22") (pin "C") (pinfunction "C_C") (pintype "passive"))
      (node (ref "VT12") (pin "2") (pinfunction "D_2") (pintype "passive"))
    )
    (net (code "84") (name "Net-(VT12-G)") (class "Default")
      (node (ref "R29") (pin "2") (pinfunction "2_2") (pintype "passive"))
      (node (ref "VT12") (pin "1") (pinfunction "G_1") (pintype "passive"))
    )
    (net (code "85") (name "unconnected-(DD1-PB2(ADC5{slash}INT1{slash}ACMPN0{slash}PCINT2)-Pad16)") (class "Default")
      (node (ref "DD1") (pin "16") (pinfunction "PB2(ADC5/INT1/ACMPN0/PCINT2)_16") (pintype "bidirectional"))
    )
    (net (code "86") (name "unconnected-(DD1-PB3(AMP0-{slash}PCINT3)-Pad23)") (class "Default")
      (node (ref "DD1") (pin "23") (pinfunction "PB3(AMP0-/PCINT3)_23") (pintype "bidirectional"))
    )
    (net (code "87") (name "unconnected-(DD1-PB4(AMP0+{slash}PCINT4)-Pad24)") (class "Default")
      (node (ref "DD1") (pin "24") (pinfunction "PB4(AMP0+/PCINT4)_24") (pintype "bidirectional"))
    )
    (net (code "88") (name "unconnected-(DD1-PB5(ADC6{slash}INT2{slash}ACMPN1{slash}AMP2-{slash}PCINT5)-Pad26)") (class "Default")
      (node (ref "DD1") (pin "26") (pinfunction "PB5(ADC6/INT2/ACMPN1/AMP2-/PCINT5)_26") (pintype "bidirectional"))
    )
    (net (code "89") (name "unconnected-(DD1-PB6(ADC7{slash}PCINT6)-Pad27)") (class "Default")
      (node (ref "DD1") (pin "27") (pinfunction "PB6(ADC7/PCINT6)_27") (pintype "bidirectional"))
    )
    (net (code "90") (name "unconnected-(DD1-PB7(ADC4{slash}SCK{slash}PCINT7)-Pad28)") (class "Default")
      (node (ref "DD1") (pin "28") (pinfunction "PB7(ADC4/SCK/PCINT7)_28") (pintype "bidirectional"))
    )
    (net (code "91") (name "unconnected-(DD1-PC0(PCINT17{slash}CLKO)-Pad30)") (class "Default")
      (node (ref "DD1") (pin "30") (pinfunction "PC0(PCINT17/CLKO)_30") (pintype "bidirectional"))
    )
    (net (code "92") (name "unconnected-(DD1-PC1(PCINT9{slash}OC1B{slash}SS_A)-Pad3)") (class "Default")
      (node (ref "DD1") (pin "3") (pinfunction "PC1(PCINT9/OC1B/SS_A)_3") (pintype "bidirectional"))
    )
    (net (code "93") (name "unconnected-(DD1-PC2(PCINT10{slash}T0{slash}TXCAN)-Pad6)") (class "Default")
      (node (ref "DD1") (pin "6") (pinfunction "PC2(PCINT10/T0/TXCAN)_6") (pintype "bidirectional"))
    )
    (net (code "94") (name "unconnected-(DD1-PC3(PCINT11{slash}T1{slash}RXCAN{slash}ICP1B)-Pad7)") (class "Default")
      (node (ref "DD1") (pin "7") (pinfunction "PC3(PCINT11/T1/RXCAN/ICP1B)_7") (pintype "bidirectional"))
    )
    (net (code "95") (name "unconnected-(DD1-PC4(ADC8{slash}ACMPN3{slash}AMP1-{slash}PCINT12)-Pad17)") (class "Default")
      (node (ref "DD1") (pin "17") (pinfunction "PC4(ADC8/ACMPN3/AMP1-/PCINT12)_17") (pintype "bidirectional"))
    )
    (net (code "96") (name "unconnected-(DD1-PC5(ADC9{slash}ACMP3{slash}AMP1+{slash}PCINT13)-Pad18)") (class "Default")
      (node (ref "DD1") (pin "18") (pinfunction "PC5(ADC9/ACMP3/AMP1+/PCINT13)_18") (pintype "bidirectional"))
    )
    (net (code "97") (name "unconnected-(DD1-PC6(ADC10-{slash}ACMP1{slash}PCINT14)-Pad22)") (class "Default")
      (node (ref "DD1") (pin "22") (pinfunction "PC6(ADC10-/ACMP1/PCINT14)_22") (pintype "bidirectional"))
    )
    (net (code "98") (name "unconnected-(DD1-PC7(D2A{slash}AMP2+{slash}PCINT15)-Pad25)") (class "Default")
      (node (ref "DD1") (pin "25") (pinfunction "PC7(D2A/AMP2+/PCINT15)_25") (pintype "bidirectional"))
    )
    (net (code "99") (name "unconnected-(DD1-PD0(PCINT16)-Pad29)") (class "Default")
      (node (ref "DD1") (pin "29") (pinfunction "PD0(PCINT16)_29") (pintype "bidirectional"))
    )
    (net (code "100") (name "unconnected-(DD1-PD1(PCINT17{slash}CLKO)-Pad32)") (class "Default")
      (node (ref "DD1") (pin "32") (pinfunction "PD1(PCINT17/CLKO)_32") (pintype "bidirectional"))
    )
    (net (code "101") (name "unconnected-(DD1-PD2(PCINT18{slash}OC1A{slash}MISO_A)-Pad1)") (class "Default")
      (node (ref "DD1") (pin "1") (pinfunction "PD2(PCINT18/OC1A/MISO_A)_1") (pintype "bidirectional"))
    )
    (net (code "102") (name "unconnected-(DD1-PD3(PCINT19{slash}TXD{slash}TXLIN{slash}OC0A{slash}MOSI_A)-Pad2)") (class "Default")
      (node (ref "DD1") (pin "2") (pinfunction "PD3(PCINT19/TXD/TXLIN/OC0A/MOSI_A)_2") (pintype "bidirectional"))
    )
    (net (code "103") (name "unconnected-(DD1-PD4(PCINT20{slash}ADC1{slash}RXD{slash}RXLIN{slash}ICP1A{slash}SCK_A)-Pad12)") (class "Default")
      (node (ref "DD1") (pin "12") (pinfunction "PD4(PCINT20/ADC1/RXD/RXLIN/ICP1A/SCK_A)_12") (pintype "bidirectional"))
    )
    (net (code "104") (name "unconnected-(DD1-PD6(ADC3{slash}ACMPN2{slash}INT0{slash}PCINT22)-Pad14)") (class "Default")
      (node (ref "DD1") (pin "14") (pinfunction "PD6(ADC3/ACMPN2/INT0/PCINT22)_14") (pintype "bidirectional"))
    )
    (net (code "105") (name "unconnected-(DD1-PD7(ACMP0{slash}PCINT23)-Pad15)") (class "Default")
      (node (ref "DD1") (pin "15") (pinfunction "PD7(ACMP0/PCINT23)_15") (pintype "bidirectional"))
    )
    (net (code "106") (name "unconnected-(DD1-PE1(PCINT25{slash}OC0B{slash}XTAL1)-Pad10)") (class "Default")
      (node (ref "DD1") (pin "10") (pinfunction "PE1(PCINT25/OC0B/XTAL1)_10") (pintype "bidirectional"))
    )
    (net (code "107") (name "unconnected-(DD1-PE2(PCINT26{slash}ADC0{slash}XTAL2)-Pad11)") (class "Default")
      (node (ref "DD1") (pin "11") (pinfunction "PE2(PCINT26/ADC0/XTAL2)_11") (pintype "bidirectional"))
    )
    (net (code "108") (name "unconnected-(DD2-PB2(ADC5{slash}INT1{slash}ACMPN0{slash}PCINT2)-Pad16)") (class "Default")
      (node (ref "DD2") (pin "16") (pinfunction "PB2(ADC5/INT1/ACMPN0/PCINT2)_16") (pintype "bidirectional"))
    )
    (net (code "109") (name "unconnected-(DD2-PB3(AMP0-{slash}PCINT3)-Pad23)") (class "Default")
      (node (ref "DD2") (pin "23") (pinfunction "PB3(AMP0-/PCINT3)_23") (pintype "bidirectional"))
    )
    (net (code "110") (name "unconnected-(DD2-PB4(AMP0+{slash}PCINT4)-Pad24)") (class "Default")
      (node (ref "DD2") (pin "24") (pinfunction "PB4(AMP0+/PCINT4)_24") (pintype "bidirectional"))
    )
    (net (code "111") (name "unconnected-(DD2-PB5(ADC6{slash}INT2{slash}ACMPN1{slash}AMP2-{slash}PCINT5)-Pad26)") (class "Default")
      (node (ref "DD2") (pin "26") (pinfunction "PB5(ADC6/INT2/ACMPN1/AMP2-/PCINT5)_26") (pintype "bidirectional"))
    )
    (net (code "112") (name "unconnected-(DD2-PB6(ADC7{slash}PCINT6)-Pad27)") (class "Default")
      (node (ref "DD2") (pin "27") (pinfunction "PB6(ADC7/PCINT6)_27") (pintype "bidirectional"))
    )
    (net (code "113") (name "unconnected-(DD2-PB7(ADC4{slash}SCK{slash}PCINT7)-Pad28)") (class "Default")
      (node (ref "DD2") (pin "28") (pinfunction "PB7(ADC4/SCK/PCINT7)_28") (pintype "bidirectional"))
    )
    (net (code "114") (name "unconnected-(DD2-PC0(PCINT17{slash}CLKO)-Pad30)") (class "Default")
      (node (ref "DD2") (pin "30") (pinfunction "PC0(PCINT17/CLKO)_30") (pintype "bidirectional"))
    )
    (net (code "115") (name "unconnected-(DD2-PC1(PCINT9{slash}OC1B{slash}SS_A)-Pad3)") (class "Default")
      (node (ref "DD2") (pin "3") (pinfunction "PC1(PCINT9/OC1B/SS_A)_3") (pintype "bidirectional"))
    )
    (net (code "116") (name "unconnected-(DD2-PC2(PCINT10{slash}T0{slash}TXCAN)-Pad6)") (class "Default")
      (node (ref "DD2") (pin "6") (pinfunction "PC2(PCINT10/T0/TXCAN)_6") (pintype "bidirectional"))
    )
    (net (code "117") (name "unconnected-(DD2-PC3(PCINT11{slash}T1{slash}RXCAN{slash}ICP1B)-Pad7)") (class "Default")
      (node (ref "DD2") (pin "7") (pinfunction "PC3(PCINT11/T1/RXCAN/ICP1B)_7") (pintype "bidirectional"))
    )
    (net (code "118") (name "unconnected-(DD2-PC4(ADC8{slash}ACMPN3{slash}AMP1-{slash}PCINT12)-Pad17)") (class "Default")
      (node (ref "DD2") (pin "17") (pinfunction "PC4(ADC8/ACMPN3/AMP1-/PCINT12)_17") (pintype "bidirectional"))
    )
    (net (code "119") (name "unconnected-(DD2-PC5(ADC9{slash}ACMP3{slash}AMP1+{slash}PCINT13)-Pad18)") (class "Default")
      (node (ref "DD2") (pin "18") (pinfunction "PC5(ADC9/ACMP3/AMP1+/PCINT13)_18") (pintype "bidirectional"))
    )
    (net (code "120") (name "unconnected-(DD2-PC6(ADC10-{slash}ACMP1{slash}PCINT14)-Pad22)") (class "Default")
      (node (ref "DD2") (pin "22") (pinfunction "PC6(ADC10-/ACMP1/PCINT14)_22") (pintype "bidirectional"))
    )
    (net (code "121") (name "unconnected-(DD2-PC7(D2A{slash}AMP2+{slash}PCINT15)-Pad25)") (class "Default")
      (node (ref "DD2") (pin "25") (pinfunction "PC7(D2A/AMP2+/PCINT15)_25") (pintype "bidirectional"))
    )
    (net (code "122") (name "unconnected-(DD2-PD0(PCINT16)-Pad29)") (class "Default")
      (node (ref "DD2") (pin "29") (pinfunction "PD0(PCINT16)_29") (pintype "bidirectional"))
    )
    (net (code "123") (name "unconnected-(DD2-PD1(PCINT17{slash}CLKO)-Pad32)") (class "Default")
      (node (ref "DD2") (pin "32") (pinfunction "PD1(PCINT17/CLKO)_32") (pintype "bidirectional"))
    )
    (net (code "124") (name "unconnected-(DD2-PD2(PCINT18{slash}OC1A{slash}MISO_A)-Pad1)") (class "Default")
      (node (ref "DD2") (pin "1") (pinfunction "PD2(PCINT18/OC1A/MISO_A)_1") (pintype "bidirectional"))
    )
    (net (code "125") (name "unconnected-(DD2-PD3(PCINT19{slash}TXD{slash}TXLIN{slash}OC0A{slash}MOSI_A)-Pad2)") (class "Default")
      (node (ref "DD2") (pin "2") (pinfunction "PD3(PCINT19/TXD/TXLIN/OC0A/MOSI_A)_2") (pintype "bidirectional"))
    )
    (net (code "126") (name "unconnected-(DD2-PD4(PCINT20{slash}ADC1{slash}RXD{slash}RXLIN{slash}ICP1A{slash}SCK_A)-Pad12)") (class "Default")
      (node (ref "DD2") (pin "12") (pinfunction "PD4(PCINT20/ADC1/RXD/RXLIN/ICP1A/SCK_A)_12") (pintype "bidirectional"))
    )
    (net (code "127") (name "unconnected-(DD2-PD6(ADC3{slash}ACMPN2{slash}INT0{slash}PCINT22)-Pad14)") (class "Default")
      (node (ref "DD2") (pin "14") (pinfunction "PD6(ADC3/ACMPN2/INT0/PCINT22)_14") (pintype "bidirectional"))
    )
    (net (code "128") (name "unconnected-(DD2-PD7(ACMP0{slash}PCINT23)-Pad15)") (class "Default")
      (node (ref "DD2") (pin "15") (pinfunction "PD7(ACMP0/PCINT23)_15") (pintype "bidirectional"))
    )
    (net (code "129") (name "unconnected-(DD2-PE1(PCINT25{slash}OC0B{slash}XTAL1)-Pad10)") (class "Default")
      (node (ref "DD2") (pin "10") (pinfunction "PE1(PCINT25/OC0B/XTAL1)_10") (pintype "bidirectional"))
    )
    (net (code "130") (name "unconnected-(DD2-PE2(PCINT26{slash}ADC0{slash}XTAL2)-Pad11)") (class "Default")
      (node (ref "DD2") (pin "11") (pinfunction "PE2(PCINT26/ADC0/XTAL2)_11") (pintype "bidirectional"))
    )
    (net (code "131") (name "unconnected-(JP1-Pad3)") (class "Default")
      (node (ref "JP1") (pin "3") (pinfunction "3_3") (pintype "passive"))
    )
    (net (code "132") (name "unconnected-(JP2-Pad3)") (class "Default")
      (node (ref "JP2") (pin "3") (pinfunction "3_3") (pintype "passive"))
    )
    (net (code "133") (name "unconnected-(TR2-3-Pad5)") (class "Default")
      (node (ref "TR2") (pin "5") (pinfunction "3_5") (pintype "passive"))
    )
    (net (code "134") (name "unconnected-(TR2-4-Pad6)") (class "Default")
      (node (ref "TR2") (pin "6") (pinfunction "4_6") (pintype "passive"))
    )
    (net (code "135") (name "unconnected-(TR4-3-Pad5)") (class "Default")
      (node (ref "TR4") (pin "5") (pinfunction "3_5") (pintype "passive"))
    )
    (net (code "136") (name "unconnected-(TR4-4-Pad6)") (class "Default")
      (node (ref "TR4") (pin "6") (pinfunction "4_6") (pintype "passive"))
    )
  )
)
